# control-interface.net
KiCad netlist of a schematic drawn in Altium Designer
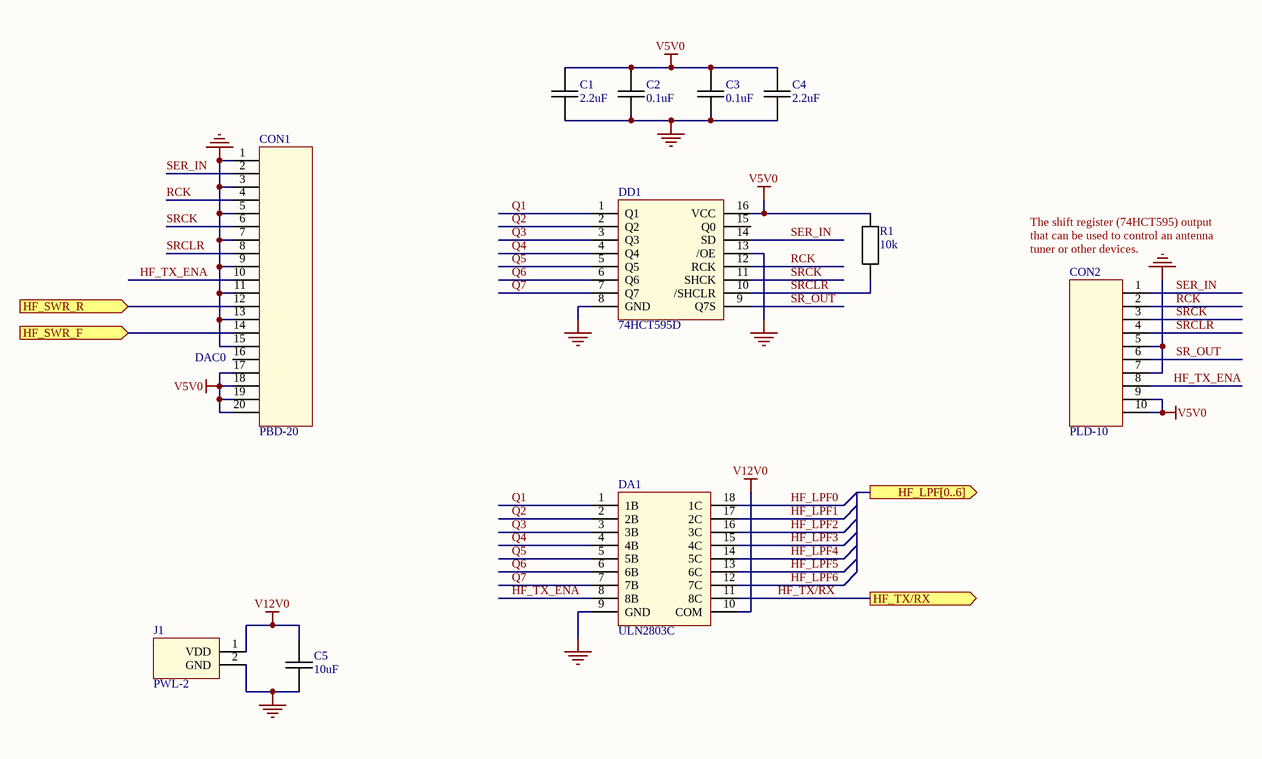
[diagram p0: control-interface.SchDoc]

(export (version "E")
  (design (tool "Eeschema 10.0.6"))
  (components
    (comp (ref "C1")
      (value "2.2uF")
      (footprint "CAPC2013X100N")
      (description "Capacitor 2x1.25 mm")
      (libsource (lib "common-lib") (part "Cap0805"))
    )
    (comp (ref "C2")
      (value "0.1uF")
      (footprint "CAPC2013X100N")
      (description "Capacitor 2x1.25 mm")
      (libsource (lib "common-lib") (part "Cap0805"))
    )
    (comp (ref "C3")
      (value "0.1uF")
      (footprint "CAPC2013X100N")
      (description "Capacitor 2x1.25 mm")
      (libsource (lib "common-lib") (part "Cap0805"))
    )
    (comp (ref "C4")
      (value "2.2uF")
      (footprint "CAPC2013X100N")
      (description "Capacitor 2x1.25 mm")
      (libsource (lib "common-lib") (part "Cap0805"))
    )
    (comp (ref "C5")
      (value "10uF")
      (footprint "CAPC2013X100N")
      (description "Capacitor 2x1.25 mm")
      (libsource (lib "common-lib") (part "Cap0805"))
    )
    (comp (ref "CON1")
      (value "PBD-20")
      (footprint "PBD-20")
      (libsource (lib "common-lib") (part "CONNECTOR-20"))
    )
    (comp (ref "CON2") (value "PLD-10") (footprint "PLD-10R") (libsource (lib "PALib") (part "CONNECTOR-10")))
    (comp (ref "DA1")
      (value "ULN2803C")
      (footprint "SOIC127P1030X265-18N")
      (description "Darlington Transistor Array")
      (libsource (lib "PALib") (part "ULN2803A"))
    )
    (comp (ref "DD1")
      (value "74HCT595D")
      (footprint "SOIC127P600X175-16N")
      (description "8-bit serial-in, serial or parallel-out shift register with output\r\nlatches; 3-state")
      (libsource (lib "PALib") (part "74HCT595D"))
    )
    (comp (ref "J1")
      (value "PWL-2")
      (footprint "PWL-2R")
      (libsource (lib "common-lib") (part "PWR_CONNECTOR"))
    )
    (comp (ref "R1") (value "10k") (footprint "RESC2013X64N") (libsource (lib "common-lib") (part "Res0805")))
  )
  (nets
    (net (code "1") (name "/HF_LPF0") (class "Default")
      (node (ref "DA1") (pin "18") (pinfunction "1C_18") (pintype "passive"))
    )
    (net (code "2") (name "/HF_LPF1") (class "Default")
      (node (ref "DA1") (pin "17") (pinfunction "2C_17") (pintype "passive"))
    )
    (net (code "3") (name "/HF_LPF2") (class "Default")
      (node (ref "DA1") (pin "16") (pinfunction "3C_16") (pintype "passive"))
    )
    (net (code "4") (name "/HF_LPF3") (class "Default")
      (node (ref "DA1") (pin "15") (pinfunction "4C_15") (pintype "passive"))
    )
    (net (code "5") (name "/HF_LPF4") (class "Default")
      (node (ref "DA1") (pin "14") (pinfunction "5C_14") (pintype "passive"))
    )
    (net (code "6") (name "/HF_LPF5") (class "Default")
      (node (ref "DA1") (pin "13") (pinfunction "6C_13") (pintype "passive"))
    )
    (net (code "7") (name "/HF_LPF6") (class "Default")
      (node (ref "DA1") (pin "12") (pinfunction "7C_12") (pintype "passive"))
    )
    (net (code "9") (name "/HF_SWR_F") (class "Default")
      (node (ref "CON1") (pin "14") (pinfunction "14_14") (pintype "passive"))
    )
    (net (code "10") (name "/HF_SWR_R") (class "Default")
      (node (ref "CON1") (pin "12") (pinfunction "12_12") (pintype "passive"))
    )
    (net (code "11") (name "/HF_TX_ENA") (class "Default")
      (node (ref "CON1") (pin "10") (pinfunction "10_10") (pintype "passive"))
      (node (ref "CON2") (pin "8") (pinfunction "8_8") (pintype "passive"))
      (node (ref "DA1") (pin "8") (pinfunction "8B_8") (pintype "passive"))
    )
    (net (code "12") (name "/HF_TX{slash}RX") (class "Default")
      (node (ref "DA1") (pin "11") (pinfunction "8C_11") (pintype "passive"))
    )
    (net (code "13") (name "/Q1") (class "Default")
      (node (ref "DA1") (pin "1") (pinfunction "1B_1") (pintype "passive"))
      (node (ref "DD1") (pin "1") (pinfunction "Q1_1") (pintype "passive"))
    )
    (net (code "14") (name "/Q2") (class "Default")
      (node (ref "DA1") (pin "2") (pinfunction "2B_2") (pintype "passive"))
      (node (ref "DD1") (pin "2") (pinfunction "Q2_2") (pintype "passive"))
    )
    (net (code "15") (name "/Q3") (class "Default")
      (node (ref "DA1") (pin "3") (pinfunction "3B_3") (pintype "passive"))
      (node (ref "DD1") (pin "3") (pinfunction "Q3_3") (pintype "passive"))
    )
    (net (code "16") (name "/Q4") (class "Default")
      (node (ref "DA1") (pin "4") (pinfunction "4B_4") (pintype "passive"))
      (node (ref "DD1") (pin "4") (pinfunction "Q4_4") (pintype "passive"))
    )
    (net (code "17") (name "/Q5") (class "Default")
      (node (ref "DA1") (pin "5") (pinfunction "5B_5") (pintype "passive"))
      (node (ref "DD1") (pin "5") (pinfunction "Q5_5") (pintype "passive"))
    )
    (net (code "18") (name "/Q6") (class "Default")
      (node (ref "DA1") (pin "6") (pinfunction "6B_6") (pintype "passive"))
      (node (ref "DD1") (pin "6") (pinfunction "Q6_6") (pintype "passive"))
    )
    (net (code "19") (name "/Q7") (class "Default")
      (node (ref "DA1") (pin "7") (pinfunction "7B_7") (pintype "passive"))
      (node (ref "DD1") (pin "7") (pinfunction "Q7_7") (pintype "passive"))
    )
    (net (code "20") (name "/RCK") (class "Default")
      (node (ref "CON1") (pin "4") (pinfunction "4_4") (pintype "passive"))
      (node (ref "CON2") (pin "2") (pinfunction "2_2") (pintype "passive"))
      (node (ref "DD1") (pin "12") (pinfunction "RCK_12") (pintype "passive"))
    )
    (net (code "21") (name "/SER_IN") (class "Default")
      (node (ref "CON1") (pin "2") (pinfunction "2_2") (pintype "passive"))
      (node (ref "CON2") (pin "1") (pinfunction "1_1") (pintype "passive"))
      (node (ref "DD1") (pin "14") (pinfunction "SD_14") (pintype "passive"))
    )
    (net (code "22") (name "/SRCK") (class "Default")
      (node (ref "CON1") (pin "6") (pinfunction "6_6") (pintype "passive"))
      (node (ref "CON2") (pin "3") (pinfunction "3_3") (pintype "passive"))
      (node (ref "DD1") (pin "11") (pinfunction "SHCK_11") (pintype "passive"))
    )
    (net (code "23") (name "/SRCLR") (class "Default")
      (node (ref "CON1") (pin "8") (pinfunction "8_8") (pintype "passive"))
      (node (ref "CON2") (pin "4") (pinfunction "4_4") (pintype "passive"))
      (node (ref "DD1") (pin "10") (pinfunction "/SHCLR_10") (pintype "passive"))
      (node (ref "R1") (pin "1") (pintype "passive"))
    )
    (net (code "24") (name "/SR_OUT") (class "Default")
      (node (ref "CON2") (pin "6") (pinfunction "6_6") (pintype "passive"))
      (node (ref "DD1") (pin "9") (pinfunction "Q7S_9") (pintype "passive"))
    )
    (net (code "25") (name "GND") (class "Default")
      (node (ref "C1") (pin "1") (pintype "passive"))
      (node (ref "C2") (pin "1") (pintype "passive"))
      (node (ref "C3") (pin "1") (pintype "passive"))
      (node (ref "C4") (pin "1") (pintype "passive"))
      (node (ref "C5") (pin "2") (pintype "passive"))
      (node (ref "CON1") (pin "1") (pinfunction "1_1") (pintype "passive"))
      (node (ref "CON1") (pin "11") (pinfunction "11_11") (pintype "passive"))
      (node (ref "CON1") (pin "13") (pinfunction "13_13") (pintype "passive"))
      (node (ref "CON1") (pin "15") (pinfunction "15_15") (pintype "passive"))
      (node (ref "CON1") (pin "3") (pinfunction "3_3") (pintype "passive"))
      (node (ref "CON1") (pin "5") (pinfunction "5_5") (pintype "passive"))
      (node (ref "CON1") (pin "7") (pinfunction "7_7") (pintype "passive"))
      (node (ref "CON1") (pin "9") (pinfunction "9_9") (pintype "passive"))
      (node (ref "CON2") (pin "5") (pinfunction "5_5") (pintype "passive"))
      (node (ref "CON2") (pin "7") (pinfunction "7_7") (pintype "passive"))
      (node (ref "DA1") (pin "9") (pinfunction "GND_9") (pintype "passive"))
      (node (ref "DD1") (pin "13") (pinfunction "/OE_13") (pintype "passive"))
      (node (ref "DD1") (pin "8") (pinfunction "GND_8") (pintype "passive"))
      (node (ref "J1") (pin "2") (pinfunction "GND_2") (pintype "power_in"))
    )
    (net (code "26") (name "V5V0") (class "Default")
      (node (ref "C1") (pin "2") (pintype "passive"))
      (node (ref "C2") (pin "2") (pintype "passive"))
      (node (ref "C3") (pin "2") (pintype "passive"))
      (node (ref "C4") (pin "2") (pintype "passive"))
      (node (ref "CON1") (pin "17") (pinfunction "17_17") (pintype "passive"))
      (node (ref "CON1") (pin "18") (pinfunction "18_18") (pintype "passive"))
      (node (ref "CON1") (pin "19") (pinfunction "19_19") (pintype "passive"))
      (node (ref "CON1") (pin "20") (pinfunction "20_20") (pintype "passive"))
      (node (ref "CON2") (pin "10") (pinfunction "10_10") (pintype "passive"))
      (node (ref "CON2") (pin "9") (pinfunction "9_9") (pintype "passive"))
      (node (ref "DD1") (pin "16") (pinfunction "VCC_16") (pintype "passive"))
      (node (ref "R1") (pin "2") (pintype "passive"))
    )
    (net (code "27") (name "V12V0") (class "Default")
      (node (ref "C5") (pin "1") (pintype "passive"))
      (node (ref "DA1") (pin "10") (pinfunction "COM_10") (pintype "passive"))
      (node (ref "J1") (pin "1") (pinfunction "VDD_1") (pintype "power_in"))
    )
    (net (code "28") (name "unconnected-(CON1-Pad16)") (class "Default")
      (node (ref "CON1") (pin "16") (pinfunction "16_16") (pintype "passive"))
    )
    (net (code "29") (name "unconnected-(DD1-Q0-Pad15)") (class "Default")
      (node (ref "DD1") (pin "15") (pinfunction "Q0_15") (pintype "passive"))
    )
  )
)
